# Module_CYW20737A1KML2G.net
KiCad netlist of a schematic drawn in Altium Designer
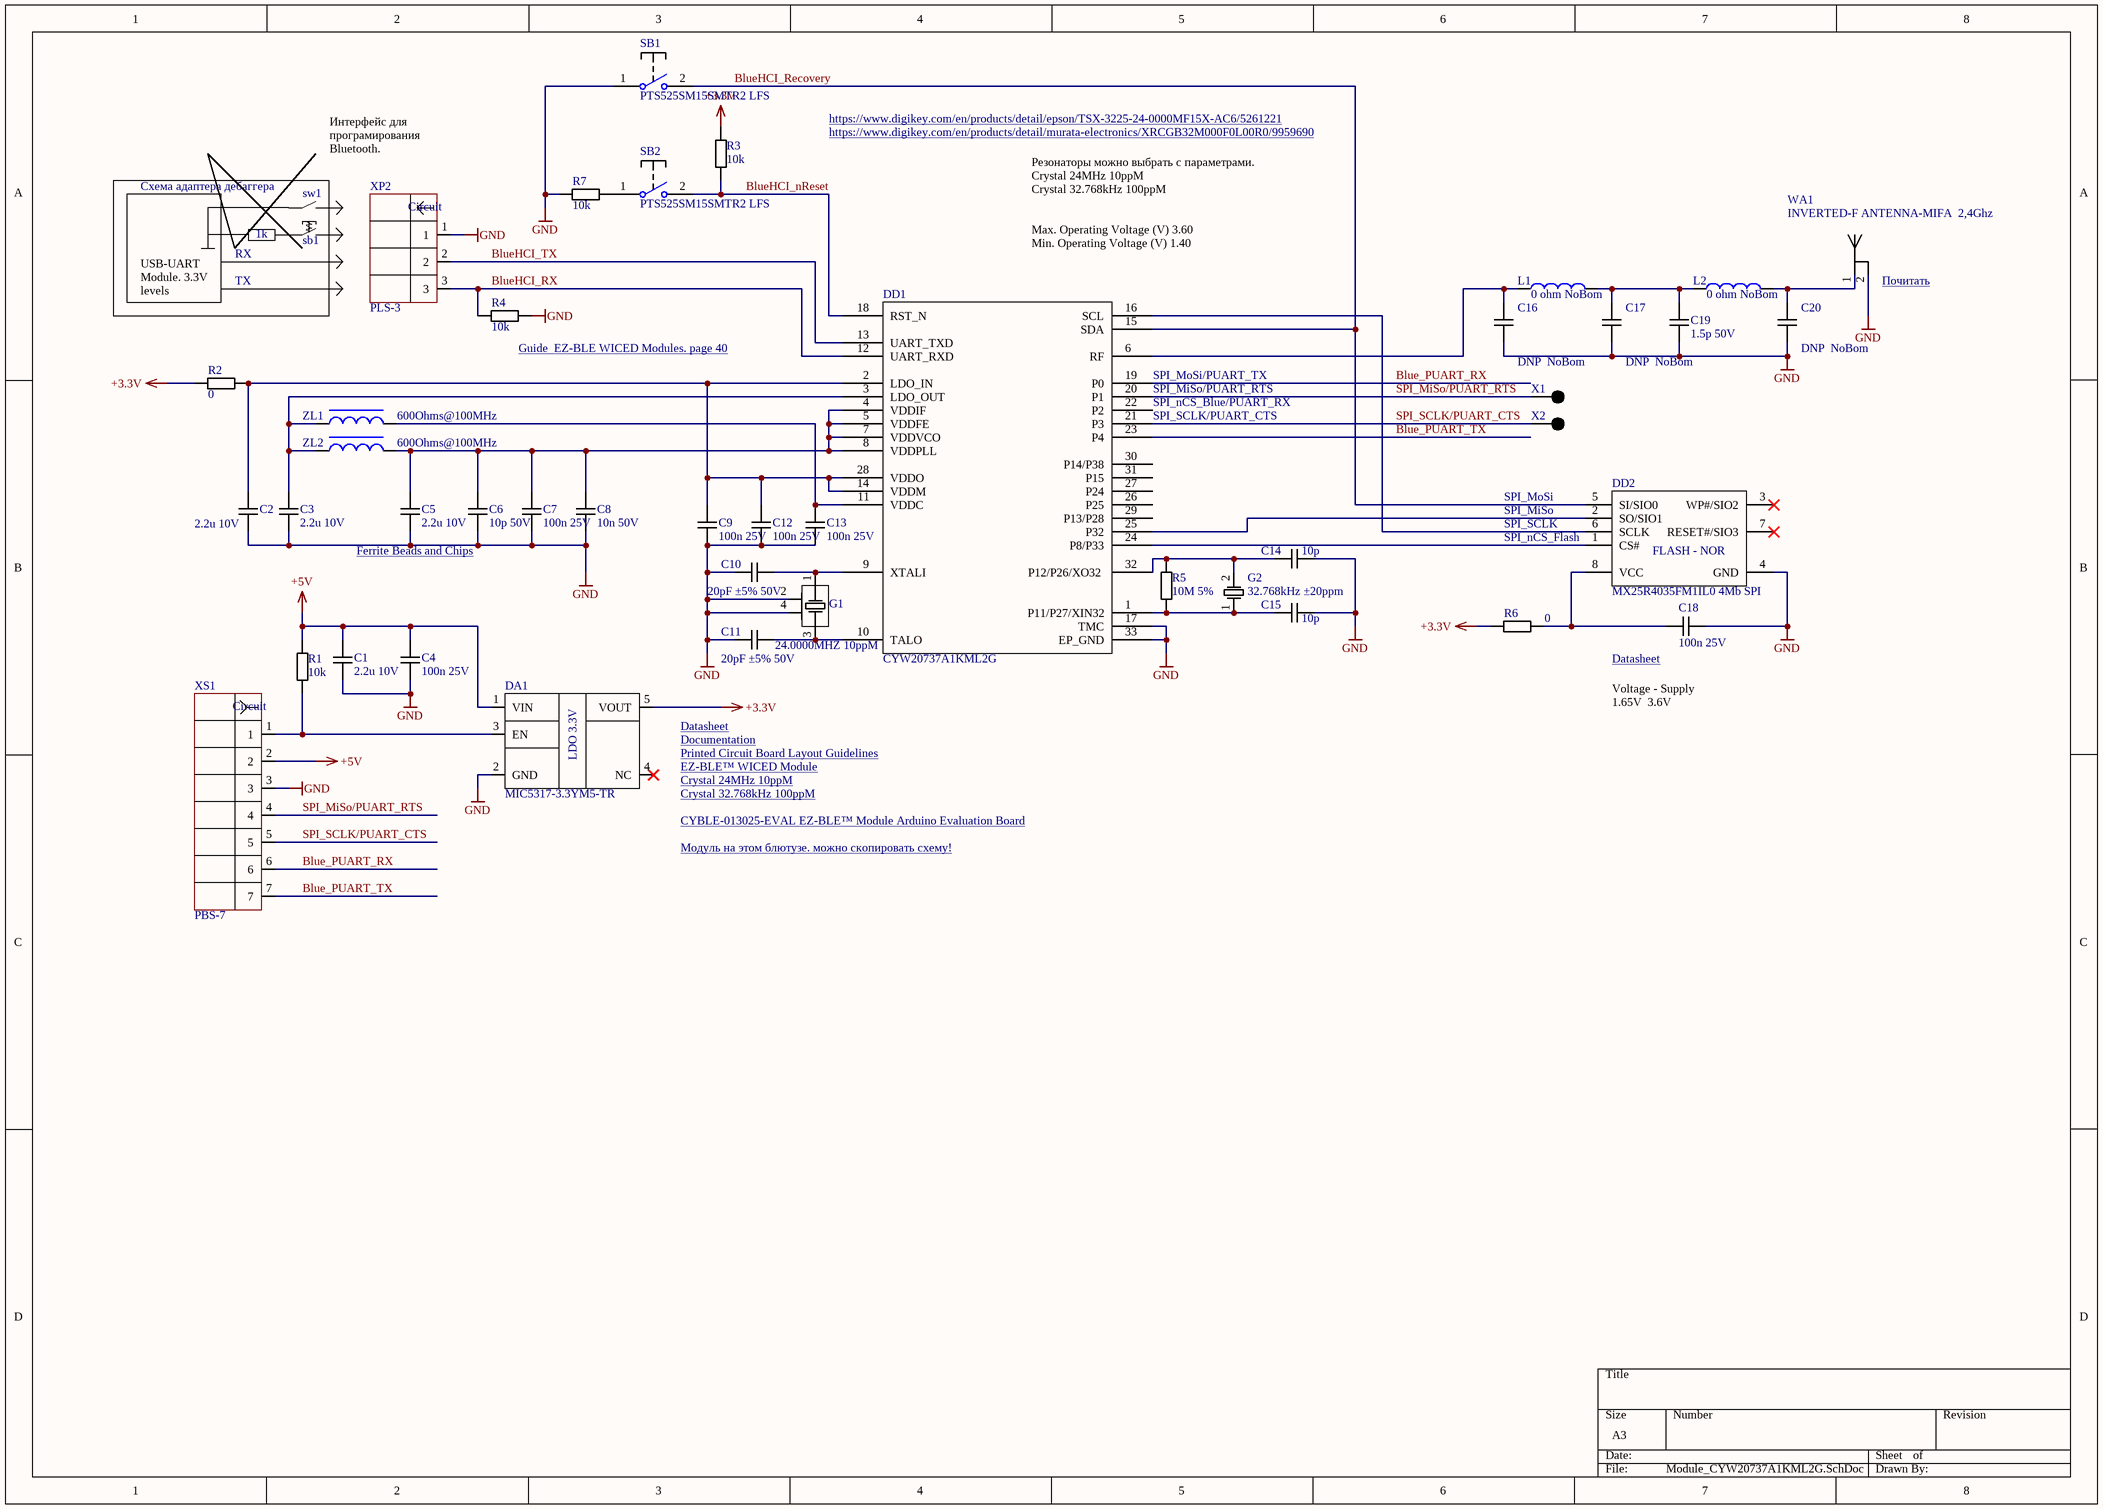
[diagram p0: Module_CYW20737A1KML2G.SchDoc]

(export (version "E")
  (design (tool "Eeschema 10.0.6"))
  (components
    (comp (ref "C1")
      (value "2.2u 10V")
      (footprint "CapKemet1005(0402)")
      (description "CAP CER 2.2uF 10V X5R 0402")
      (fields
        (field (name "PART NUMBER") "LMK105BJ225MV-F")
        (field (name "DIGI-KEY PART NUMBER") "587-3153-1-ND")
      )
      (libsource (lib "SssAccesDatbase") (part "Cap"))
    )
    (comp (ref "C2")
      (value "2.2u 10V")
      (footprint "CapKemet1005(0402)")
      (description "CAP CER 2.2uF 10V X5R 0402")
      (fields
        (field (name "PART NUMBER") "LMK105BJ225MV-F")
        (field (name "DIGI-KEY PART NUMBER") "587-3153-1-ND")
      )
      (libsource (lib "SssAccesDatbase") (part "Cap"))
    )
    (comp (ref "C3")
      (value "2.2u 10V")
      (footprint "CapKemet1005(0402)")
      (description "CAP CER 2.2uF 10V X5R 0402")
      (fields
        (field (name "PART NUMBER") "LMK105BJ225MV-F")
        (field (name "DIGI-KEY PART NUMBER") "587-3153-1-ND")
      )
      (libsource (lib "SssAccesDatbase") (part "Cap"))
    )
    (comp (ref "C4")
      (value "100n 25V")
      (footprint "CapKemet1005(0402)")
      (description "CAP CER 0.1UF 25V X7R 0402")
      (fields
        (field (name "PART NUMBER") "CL05B104KA5NNNC")
        (field (name "DIGI-KEY PART NUMBER") "1276-6720-1-ND")
      )
      (libsource (lib "SssAccesDatbase") (part "Cap"))
    )
    (comp (ref "C5")
      (value "2.2u 10V")
      (footprint "CapKemet1005(0402)")
      (description "CAP CER 2.2uF 10V X5R 0402")
      (fields
        (field (name "PART NUMBER") "LMK105BJ225MV-F")
        (field (name "DIGI-KEY PART NUMBER") "587-3153-1-ND")
      )
      (libsource (lib "SssAccesDatbase") (part "Cap"))
    )
    (comp (ref "C6")
      (value "10p 50V")
      (footprint "CapKemet1005(0402)")
      (description "CAP CER 10PF 50V C0G/NP0 0402")
      (fields
        (field (name "PART NUMBER") "CL05C100DB5NNNC")
        (field (name "DIGI-KEY PART NUMBER") "1276-1625-1-ND")
      )
      (libsource (lib "SssAccesDatbase") (part "Cap"))
    )
    (comp (ref "C7")
      (value "100n 25V")
      (footprint "CapKemet1005(0402)")
      (description "CAP CER 0.1UF 25V X7R 0402")
      (fields
        (field (name "PART NUMBER") "CL05B104KA5NNNC")
        (field (name "DIGI-KEY PART NUMBER") "1276-6720-1-ND")
      )
      (libsource (lib "SssAccesDatbase") (part "Cap"))
    )
    (comp (ref "C8")
      (value "10n 50V")
      (footprint "CapKemet1005(0402)")
      (description "CAP CER 10000PF 50V X7R 0402")
      (fields
        (field (name "PART NUMBER") "CL05B103KB5NNNC")
        (field (name "DIGI-KEY PART NUMBER") "1276-1028-1-ND")
      )
      (libsource (lib "SssAccesDatbase") (part "Cap"))
    )
    (comp (ref "C9")
      (value "100n 25V")
      (footprint "CapKemet1005(0402)")
      (description "CAP CER 0.1UF 25V X7R 0402")
      (fields
        (field (name "PART NUMBER") "CL05B104KA5NNNC")
        (field (name "DIGI-KEY PART NUMBER") "1276-6720-1-ND")
      )
      (libsource (lib "SssAccesDatbase") (part "Cap"))
    )
    (comp (ref "C10")
      (value "20pF ±5% 50V")
      (footprint "CapKemet1005(0402)")
      (description "20pF ±5% 50V Ceramic Capacitor C0G, NP0 0402 (1005 Metric)")
      (fields
        (field (name "PART NUMBER") "CC0402JRNPO9BN200")
        (field (name "DIGI-KEY PART NUMBER") "311-1417-1-ND")
      )
      (libsource (lib "SssAccesDatbase") (part "Cap"))
    )
    (comp (ref "C11")
      (value "20pF ±5% 50V")
      (footprint "CapKemet1005(0402)")
      (description "20pF ±5% 50V Ceramic Capacitor C0G, NP0 0402 (1005 Metric)")
      (fields
        (field (name "PART NUMBER") "CC0402JRNPO9BN200")
        (field (name "DIGI-KEY PART NUMBER") "311-1417-1-ND")
      )
      (libsource (lib "SssAccesDatbase") (part "Cap"))
    )
    (comp (ref "C12")
      (value "100n 25V")
      (footprint "CapKemet1005(0402)")
      (description "CAP CER 0.1UF 25V X7R 0402")
      (fields
        (field (name "PART NUMBER") "CL05B104KA5NNNC")
        (field (name "DIGI-KEY PART NUMBER") "1276-6720-1-ND")
      )
      (libsource (lib "SssAccesDatbase") (part "Cap"))
    )
    (comp (ref "C13")
      (value "100n 25V")
      (footprint "CapKemet1005(0402)")
      (description "CAP CER 0.1UF 25V X7R 0402")
      (fields
        (field (name "PART NUMBER") "CL05B104KA5NNNC")
        (field (name "DIGI-KEY PART NUMBER") "1276-6720-1-ND")
      )
      (libsource (lib "SssAccesDatbase") (part "Cap"))
    )
    (comp (ref "C14")
      (value "10p")
      (footprint "CapKemet1005(0402)")
      (description "10pF 0402 50V C0G  +/-0.5pF")
      (fields
        (field (name "PART NUMBER") "CC0402DRNPO9BN100")
        (field (name "MOUSER PART NUMBER") "603-CC402DRNPO9BN100")
      )
      (libsource (lib "SssAccesDatbase") (part "Cap"))
    )
    (comp (ref "C15")
      (value "10p")
      (footprint "CapKemet1005(0402)")
      (description "10pF 0402 50V C0G  +/-0.5pF")
      (fields
        (field (name "PART NUMBER") "CC0402DRNPO9BN100")
        (field (name "MOUSER PART NUMBER") "603-CC402DRNPO9BN100")
      )
      (libsource (lib "SssAccesDatbase") (part "Cap"))
    )
    (comp (ref "C16")
      (value "DNP  NoBom")
      (footprint "CapKemet1005(0402)")
      (description "150pF 0402 50V NP0  +/-5%")
      (fields
        (field (name "PART NUMBER") "GCM1555C1H151JA16D")
        (field (name "MOUSER PART NUMBER") "81-GCM1555C1H151J16D")
      )
      (libsource (lib "SssAccesDatbase") (part "Cap"))
    )
    (comp (ref "C17")
      (value "DNP  NoBom")
      (footprint "CapKemet1005(0402)")
      (description "150pF 0402 50V NP0  +/-5%")
      (fields
        (field (name "PART NUMBER") "GCM1555C1H151JA16D")
        (field (name "MOUSER PART NUMBER") "81-GCM1555C1H151J16D")
      )
      (libsource (lib "SssAccesDatbase") (part "Cap"))
    )
    (comp (ref "C18")
      (value "100n 25V")
      (footprint "CapKemet1005(0402)")
      (description "CAP CER 0.1UF 25V X7R 0402")
      (fields
        (field (name "PART NUMBER") "CL05B104KA5NNNC")
        (field (name "DIGI-KEY PART NUMBER") "1276-6720-1-ND")
      )
      (libsource (lib "SssAccesDatbase") (part "Cap"))
    )
    (comp (ref "C19")
      (value "1.5p 50V")
      (footprint "CapKemet1005(0402)")
      (description "CAP CER 1.5pF 50V COG 0402 ±0.1pF")
      (fields
        (field (name "PART NUMBER") "CL05C1R5BB5NNNC")
        (field (name "DIGI-KEY PART NUMBER") "1276-1656-1-ND")
      )
      (libsource (lib "SssAccesDatbase") (part "Cap"))
    )
    (comp (ref "C20")
      (value "DNP  NoBom")
      (footprint "CapKemet1005(0402)")
      (description "150pF 0402 50V NP0  +/-5%")
      (fields
        (field (name "PART NUMBER") "GCM1555C1H151JA16D")
        (field (name "MOUSER PART NUMBER") "81-GCM1555C1H151J16D")
      )
      (libsource (lib "SssAccesDatbase") (part "Cap"))
    )
    (comp (ref "DA1")
      (value "MIC5317-3.3YM5-TR")
      (footprint "SOT-23-OT5_N")
      (description "Linear Voltage Regulator IC 1 Output 150mA SOT-23-5")
      (fields (field (name "DIGI-KEY PART NUMBER") "MIC5317-3.3YM5-CT-ND"))
      (libsource (lib "SssAccesDatbase") (part "MIC5317-3.3YM5-TR"))
    )
    (comp (ref "DD1")
      (value "CYW20737A1KML2G")
      (footprint "QFN5X5-32_N")
      (description "IC RF TXRX+MCU BLUETOOTH 32VFQFN")
      (fields (field (name "DIGI-KEY PART NUMBER") "2015-CYW20737A1KML2G-ND"))
      (libsource (lib "SssAccesDatbase") (part "CYW20737A1KML2G"))
    )
    (comp (ref "DD2")
      (value "MX25R4035FM1IL0 4Mb SPI")
      (footprint "MCHP-SOIC-SN8_M")
      (description "IC FLASH 4M SPI 33MHZ 8SOP")
      (fields (field (name "PART NUMBER") "MX25R4035FM1IL0"))
      (libsource (lib "SssAccesDatbase") (part "MX25R4035FM1IL0"))
    )
    (comp (ref "G1")
      (value "24.0000MHZ 10ppM")
      (footprint "TSX-3225")
      (description "24MHz ±10ppm Crystal 9pF 40 Ohms 4-SMD, No Lead")
      (fields
        (field (name "PART NUMBER") "TSX-3225 24.0000MF15X-AC6")
        (field (name "DIGI-KEY PART NUMBER") "SER4180CT-ND")
      )
      (libsource (lib "SssAccesDatbase") (part "CTX957CT"))
    )
    (comp (ref "G2")
      (value "32.768kHz ±20ppm")
      (footprint "VMK3-9005")
      (description "32.768kHz ±20ppm Crystal   2-SMD, No Lead")
      (fields
        (field (name "PART NUMBER") "VMK3-9005-32K7680000")
        (field (name "DIGI-KEY PART NUMBER") "150-VMK3-9005-32K7680000CT-ND")
      )
      (libsource (lib "SssAccesDatbase") (part "Crystal"))
    )
    (comp (ref "L1")
      (value "0 ohm NoBom")
      (footprint "INDC1608(0603)N")
      (description "Fixed Inductors 270nH 2% -40C +125C")
      (fields
        (field (name "PART NUMBER") "AISC-0603-R27G-T")
        (field (name "MOUSER PART NUMBER") "815-AISC0603R27GT")
      )
      (libsource (lib "SssAccesDatbase") (part "L"))
    )
    (comp (ref "L2")
      (value "0 ohm NoBom")
      (footprint "INDC1608(0603)N")
      (description "Fixed Inductors 270nH 2% -40C +125C")
      (fields
        (field (name "PART NUMBER") "AISC-0603-R27G-T")
        (field (name "MOUSER PART NUMBER") "815-AISC0603R27GT")
      )
      (libsource (lib "SssAccesDatbase") (part "L"))
    )
    (comp (ref "R1")
      (value "10k")
      (footprint "REZKemet 0402")
      (description "RES SMD 5.1K OHM 1% 1/10W 0402")
      (fields
        (field (name "PART NUMBER") "RESC1005(0402)")
        (field (name "MANUFACTURER PART NUMBER") "ERJ-2RKF5101X")
      )
      (libsource (lib "SssAccesDatbase") (part "Resistor general"))
    )
    (comp (ref "R2")
      (value "0")
      (footprint "REZKemet 0402")
      (description "RES SMD 0402 0 Ohm")
      (fields
        (field (name "PART NUMBER") "RMCF0402ZT0R00")
        (field (name "MOUSER PART NUMBER") "RMCF0402ZT0R00CT-ND")
      )
      (libsource (lib "") (part "Resistor general_4"))
    )
    (comp (ref "R3")
      (value "10k")
      (footprint "REZKemet 0402")
      (description "RES SMD 5.1K OHM 1% 1/10W 0402")
      (fields
        (field (name "PART NUMBER") "RESC1005(0402)")
        (field (name "MANUFACTURER PART NUMBER") "ERJ-2RKF5101X")
      )
      (libsource (lib "SssAccesDatbase") (part "Resistor general"))
    )
    (comp (ref "R4")
      (value "10k")
      (footprint "REZKemet 0402")
      (description "RES SMD 5.1K OHM 1% 1/10W 0402")
      (fields
        (field (name "PART NUMBER") "RESC1005(0402)")
        (field (name "MANUFACTURER PART NUMBER") "ERJ-2RKF5101X")
      )
      (libsource (lib "") (part "Resistor general_1"))
    )
    (comp (ref "R5")
      (value "10M 5%")
      (footprint "REZKemet 0402")
      (description "RES SMD 0402 10 MOhm 5% 200ppm")
      (fields
        (field (name "PART NUMBER") "RMCF0402JT10M0")
        (field (name "DIGI-KEY PART NUMBER") "RMCF0402JT10M0CT-ND")
      )
      (libsource (lib "") (part "Resistor general_2"))
    )
    (comp (ref "R6")
      (value "0")
      (footprint "REZKemet 0402")
      (description "RES SMD 0402 0 Ohm")
      (fields
        (field (name "PART NUMBER") "RMCF0402ZT0R00")
        (field (name "MOUSER PART NUMBER") "RMCF0402ZT0R00CT-ND")
      )
      (libsource (lib "") (part "Resistor general_3"))
    )
    (comp (ref "R7")
      (value "10k")
      (footprint "REZKemet 0402")
      (description "RES SMD 5.1K OHM 1% 1/10W 0402")
      (fields
        (field (name "PART NUMBER") "RESC1005(0402)")
        (field (name "MANUFACTURER PART NUMBER") "ERJ-2RKF5101X")
      )
      (libsource (lib "") (part "Resistor general_1"))
    )
    (comp (ref "SB1")
      (value "PTS525SM15SMTR2 LFS")
      (footprint "TACT_SWITCH KPT1187B")
      (description "SWITCH TACTILE SPST-NO 0.02A 15V")
      (fields (field (name "DIGI-KEY PART NUMBER") "CKN9104CT-ND"))
      (libsource (lib "SssAccesDatbase") (part "TACT_SWITCH KPT1187B"))
    )
    (comp (ref "SB2")
      (value "PTS525SM15SMTR2 LFS")
      (footprint "TACT_SWITCH KPT1187B")
      (description "SWITCH TACTILE SPST-NO 0.02A 15V")
      (fields (field (name "DIGI-KEY PART NUMBER") "CKN9104CT-ND"))
      (libsource (lib "SssAccesDatbase") (part "TACT_SWITCH KPT1187B"))
    )
    (comp (ref "WA1")
      (value "INVERTED-F ANTENNA-MIFA  2,4Ghz")
      (footprint "INVERTED-F ANTENNA-MIFA")
      (libsource (lib "SssAccesDatbase") (part "WA_2pin_tie"))
    )
    (comp (ref "X1")
      (value "PLLS1.27-1-TOP-R")
      (footprint "PLLS1.27-1-TOP-R")
      (libsource (lib "SssAccesDatbase") (part "X1_1"))
    )
    (comp (ref "X2")
      (value "PLLS1.27-1-TOP-R")
      (footprint "PLLS1.27-1-TOP-R")
      (libsource (lib "SssAccesDatbase") (part "X1_1"))
    )
    (comp (ref "XP2")
      (value "PLS-3")
      (footprint "PLS-3-3D")
      (description "CONN HEADER VERT 3POS 2.54MM")
      (fields
        (field (name "DIGI-KEY PART NUMBER") "1849-1003-ND")
        (field (name "MANUFACTURER PART NUMBER") "PR20203VBNN")
      )
      (libsource (lib "SssAccesDatbase") (part "XP-3"))
    )
    (comp (ref "XS1")
      (value "PBS-7")
      (footprint "PBS-7-3D")
      (libsource (lib "SssAccesDatbase") (part "XS-7"))
    )
    (comp (ref "ZL1")
      (value "600Ohms@100MHz")
      (footprint "Ferrite1005(0402)")
      (description "FERRITE BEAD 600 OHM 0402 1LN")
      (fields
        (field (name "PART NUMBER") "MMZ1005S601CT000")
        (field (name "DIGI-KEY PART NUMBER") "445-2162-1-ND")
      )
      (libsource (lib "SssAccesDatbase") (part "ZL"))
    )
    (comp (ref "ZL2")
      (value "600Ohms@100MHz")
      (footprint "Ferrite1005(0402)")
      (description "FERRITE BEAD 600 OHM 0402 1LN")
      (fields
        (field (name "PART NUMBER") "MMZ1005S601CT000")
        (field (name "DIGI-KEY PART NUMBER") "445-2162-1-ND")
      )
      (libsource (lib "SssAccesDatbase") (part "ZL"))
    )
  )
  (nets
    (net (code "1") (name "+3.3V") (class "Default")
      (node (ref "DA1") (pin "5") (pinfunction "VOUT_5") (pintype "passive"))
      (node (ref "R2") (pin "2") (pinfunction "2_2") (pintype "passive"))
      (node (ref "R3") (pin "2") (pinfunction "2_2") (pintype "passive"))
      (node (ref "R6") (pin "1") (pinfunction "1_1") (pintype "passive"))
    )
    (net (code "2") (name "+5V") (class "Default")
      (node (ref "C1") (pin "2") (pinfunction "2_2") (pintype "passive"))
      (node (ref "C4") (pin "2") (pinfunction "2_2") (pintype "passive"))
      (node (ref "DA1") (pin "1") (pinfunction "VIN_1") (pintype "passive"))
      (node (ref "R1") (pin "2") (pinfunction "2_2") (pintype "passive"))
      (node (ref "XS1") (pin "2") (pinfunction "2_2") (pintype "passive"))
    )
    (net (code "3") (name "/BlueHCI_RX") (class "Default")
      (node (ref "DD1") (pin "12") (pinfunction "UART_RXD_12") (pintype "passive"))
      (node (ref "R4") (pin "2") (pinfunction "2_2") (pintype "passive"))
      (node (ref "XP2") (pin "3") (pinfunction "3_3") (pintype "passive"))
    )
    (net (code "4") (name "/BlueHCI_Recovery") (class "Default")
      (node (ref "DD1") (pin "15") (pinfunction "SDA_15") (pintype "passive"))
      (node (ref "DD2") (pin "5") (pinfunction "SI/SIO0_5") (pintype "passive"))
      (node (ref "SB1") (pin "2") (pinfunction "NO_2") (pintype "passive"))
    )
    (net (code "5") (name "/BlueHCI_TX") (class "Default")
      (node (ref "DD1") (pin "13") (pinfunction "UART_TXD_13") (pintype "passive"))
      (node (ref "XP2") (pin "2") (pinfunction "2_2") (pintype "passive"))
    )
    (net (code "6") (name "/BlueHCI_nReset") (class "Default")
      (node (ref "DD1") (pin "18") (pinfunction "RST_N_18") (pintype "passive"))
      (node (ref "R3") (pin "1") (pinfunction "1_1") (pintype "passive"))
      (node (ref "SB2") (pin "2") (pinfunction "NO_2") (pintype "passive"))
    )
    (net (code "7") (name "/Blue_PUART_RX") (class "Default")
      (node (ref "DD1") (pin "19") (pinfunction "P0_19") (pintype "passive"))
      (node (ref "XS1") (pin "6") (pinfunction "6_6") (pintype "passive"))
    )
    (net (code "8") (name "/Blue_PUART_TX") (class "Default")
      (node (ref "DD1") (pin "23") (pinfunction "P4_23") (pintype "passive"))
      (node (ref "XS1") (pin "7") (pinfunction "7_7") (pintype "passive"))
    )
    (net (code "9") (name "/SPI_MiSo{slash}PUART_RTS") (class "Default")
      (node (ref "DD1") (pin "20") (pinfunction "P1_20") (pintype "passive"))
      (node (ref "X1") (pin "1") (pinfunction "1_1") (pintype "passive"))
      (node (ref "XS1") (pin "4") (pinfunction "4_4") (pintype "passive"))
    )
    (net (code "10") (name "/SPI_SCLK{slash}PUART_CTS") (class "Default")
      (node (ref "DD1") (pin "21") (pinfunction "P3_21") (pintype "passive"))
      (node (ref "X2") (pin "1") (pinfunction "1_1") (pintype "passive"))
      (node (ref "XS1") (pin "5") (pinfunction "5_5") (pintype "passive"))
    )
    (net (code "11") (name "GND") (class "Default")
      (node (ref "C1") (pin "1") (pinfunction "1_1") (pintype "passive"))
      (node (ref "C10") (pin "1") (pinfunction "1_1") (pintype "passive"))
      (node (ref "C11") (pin "1") (pinfunction "1_1") (pintype "passive"))
      (node (ref "C12") (pin "1") (pinfunction "1_1") (pintype "passive"))
      (node (ref "C13") (pin "1") (pinfunction "1_1") (pintype "passive"))
      (node (ref "C14") (pin "1") (pinfunction "1_1") (pintype "passive"))
      (node (ref "C15") (pin "1") (pinfunction "1_1") (pintype "passive"))
      (node (ref "C16") (pin "1") (pinfunction "1_1") (pintype "passive"))
      (node (ref "C17") (pin "1") (pinfunction "1_1") (pintype "passive"))
      (node (ref "C18") (pin "1") (pinfunction "1_1") (pintype "passive"))
      (node (ref "C19") (pin "1") (pinfunction "1_1") (pintype "passive"))
      (node (ref "C2") (pin "1") (pinfunction "1_1") (pintype "passive"))
      (node (ref "C20") (pin "1") (pinfunction "1_1") (pintype "passive"))
      (node (ref "C3") (pin "1") (pinfunction "1_1") (pintype "passive"))
      (node (ref "C4") (pin "1") (pinfunction "1_1") (pintype "passive"))
      (node (ref "C5") (pin "1") (pinfunction "1_1") (pintype "passive"))
      (node (ref "C6") (pin "1") (pinfunction "1_1") (pintype "passive"))
      (node (ref "C7") (pin "1") (pinfunction "1_1") (pintype "passive"))
      (node (ref "C8") (pin "1") (pinfunction "1_1") (pintype "passive"))
      (node (ref "C9") (pin "1") (pinfunction "1_1") (pintype "passive"))
      (node (ref "DA1") (pin "2") (pinfunction "GND_2") (pintype "passive"))
      (node (ref "DD1") (pin "17") (pinfunction "TMC_17") (pintype "passive"))
      (node (ref "DD1") (pin "33") (pinfunction "EP_GND_33") (pintype "passive"))
      (node (ref "DD2") (pin "4") (pinfunction "GND_4") (pintype "passive"))
      (node (ref "G1") (pin "2") (pinfunction "2_2") (pintype "passive"))
      (node (ref "G1") (pin "4") (pinfunction "4_4") (pintype "passive"))
      (node (ref "R4") (pin "1") (pinfunction "1_1") (pintype "passive"))
      (node (ref "R7") (pin "2") (pinfunction "2_2") (pintype "passive"))
      (node (ref "SB1") (pin "1") (pinfunction "COMMON_1") (pintype "passive"))
      (node (ref "WA1") (pin "2") (pinfunction "2_2") (pintype "passive"))
      (node (ref "XP2") (pin "1") (pinfunction "1_1") (pintype "passive"))
      (node (ref "XS1") (pin "3") (pinfunction "3_3") (pintype "passive"))
    )
    (net (code "12") (name "Net-(C17-Pad2)") (class "Default")
      (node (ref "C17") (pin "2") (pinfunction "2_2") (pintype "passive"))
      (node (ref "C19") (pin "2") (pinfunction "2_2") (pintype "passive"))
      (node (ref "L1") (pin "2") (pinfunction "2_2") (pintype "passive"))
      (node (ref "L2") (pin "1") (pinfunction "1_1") (pintype "passive"))
    )
    (net (code "13") (name "Net-(C20-Pad2)") (class "Default")
      (node (ref "C20") (pin "2") (pinfunction "2_2") (pintype "passive"))
      (node (ref "L2") (pin "2") (pinfunction "2_2") (pintype "passive"))
      (node (ref "WA1") (pin "1") (pinfunction "1_1") (pintype "passive"))
    )
    (net (code "14") (name "Net-(DA1-EN)") (class "Default")
      (node (ref "DA1") (pin "3") (pinfunction "EN_3") (pintype "passive"))
      (node (ref "R1") (pin "1") (pinfunction "1_1") (pintype "passive"))
      (node (ref "XS1") (pin "1") (pinfunction "1_1") (pintype "passive"))
    )
    (net (code "15") (name "Net-(DD1-LDO_IN)") (class "Default")
      (node (ref "C12") (pin "2") (pinfunction "2_2") (pintype "passive"))
      (node (ref "C2") (pin "2") (pinfunction "2_2") (pintype "passive"))
      (node (ref "C9") (pin "2") (pinfunction "2_2") (pintype "passive"))
      (node (ref "DD1") (pin "14") (pinfunction "VDDM_14") (pintype "passive"))
      (node (ref "DD1") (pin "2") (pinfunction "LDO_IN_2") (pintype "passive"))
      (node (ref "DD1") (pin "28") (pinfunction "VDDO_28") (pintype "passive"))
      (node (ref "R2") (pin "1") (pinfunction "1_1") (pintype "passive"))
    )
    (net (code "16") (name "Net-(DD1-LDO_OUT)") (class "Default")
      (node (ref "C3") (pin "2") (pinfunction "2_2") (pintype "passive"))
      (node (ref "DD1") (pin "3") (pinfunction "LDO_OUT_3") (pintype "passive"))
      (node (ref "ZL1") (pin "1") (pinfunction "1_1") (pintype "passive"))
      (node (ref "ZL2") (pin "1") (pinfunction "1_1") (pintype "passive"))
    )
    (net (code "17") (name "Net-(DD1-P8{slash}P33)") (class "Default")
      (node (ref "DD1") (pin "24") (pinfunction "P8/P33_24") (pintype "passive"))
      (node (ref "DD2") (pin "1") (pinfunction "CS#_1") (pintype "passive"))
    )
    (net (code "18") (name "Net-(DD1-P11{slash}P27{slash}XIN32)") (class "Default")
      (node (ref "C15") (pin "2") (pinfunction "2_2") (pintype "passive"))
      (node (ref "DD1") (pin "1") (pinfunction "P11/P27/XIN32_1") (pintype "passive"))
      (node (ref "G2") (pin "1") (pinfunction "1_1") (pintype "passive"))
      (node (ref "R5") (pin "1") (pinfunction "1_1") (pintype "passive"))
    )
    (net (code "19") (name "Net-(DD1-P12{slash}P26{slash}XO32)") (class "Default")
      (node (ref "C14") (pin "2") (pinfunction "2_2") (pintype "passive"))
      (node (ref "DD1") (pin "32") (pinfunction "P12/P26/XO32_32") (pintype "passive"))
      (node (ref "G2") (pin "2") (pinfunction "2_2") (pintype "passive"))
      (node (ref "R5") (pin "2") (pinfunction "2_2") (pintype "passive"))
    )
    (net (code "20") (name "Net-(DD1-P32)") (class "Default")
      (node (ref "DD1") (pin "25") (pinfunction "P32_25") (pintype "passive"))
      (node (ref "DD2") (pin "2") (pinfunction "SO/SIO1_2") (pintype "passive"))
    )
    (net (code "21") (name "Net-(DD1-RF)") (class "Default")
      (node (ref "C16") (pin "2") (pinfunction "2_2") (pintype "passive"))
      (node (ref "DD1") (pin "6") (pinfunction "RF_6") (pintype "passive"))
      (node (ref "L1") (pin "1") (pinfunction "1_1") (pintype "passive"))
    )
    (net (code "22") (name "Net-(DD1-SCL)") (class "Default")
      (node (ref "DD1") (pin "16") (pinfunction "SCL_16") (pintype "passive"))
      (node (ref "DD2") (pin "6") (pinfunction "SCLK_6") (pintype "passive"))
    )
    (net (code "23") (name "Net-(DD1-TALO)") (class "Default")
      (node (ref "C11") (pin "2") (pinfunction "2_2") (pintype "passive"))
      (node (ref "DD1") (pin "10") (pinfunction "TALO_10") (pintype "passive"))
      (node (ref "G1") (pin "3") (pinfunction "3_3") (pintype "passive"))
    )
    (net (code "24") (name "Net-(DD1-VDDC)") (class "Default")
      (node (ref "C13") (pin "2") (pinfunction "2_2") (pintype "passive"))
      (node (ref "DD1") (pin "11") (pinfunction "VDDC_11") (pintype "passive"))
      (node (ref "ZL1") (pin "2") (pinfunction "2_2") (pintype "passive"))
    )
    (net (code "25") (name "Net-(DD1-VDDFE)") (class "Default")
      (node (ref "C5") (pin "2") (pinfunction "2_2") (pintype "passive"))
      (node (ref "C6") (pin "2") (pinfunction "2_2") (pintype "passive"))
      (node (ref "C7") (pin "2") (pinfunction "2_2") (pintype "passive"))
      (node (ref "C8") (pin "2") (pinfunction "2_2") (pintype "passive"))
      (node (ref "DD1") (pin "4") (pinfunction "VDDIF_4") (pintype "passive"))
      (node (ref "DD1") (pin "5") (pinfunction "VDDFE_5") (pintype "passive"))
      (node (ref "DD1") (pin "7") (pinfunction "VDDVCO_7") (pintype "passive"))
      (node (ref "DD1") (pin "8") (pinfunction "VDDPLL_8") (pintype "passive"))
      (node (ref "ZL2") (pin "2") (pinfunction "2_2") (pintype "passive"))
    )
    (net (code "26") (name "Net-(DD1-XTALI)") (class "Default")
      (node (ref "C10") (pin "2") (pinfunction "2_2") (pintype "passive"))
      (node (ref "DD1") (pin "9") (pinfunction "XTALI_9") (pintype "passive"))
      (node (ref "G1") (pin "1") (pinfunction "1_1") (pintype "passive"))
    )
    (net (code "27") (name "Net-(DD2-VCC)") (class "Default")
      (node (ref "C18") (pin "2") (pinfunction "2_2") (pintype "passive"))
      (node (ref "DD2") (pin "8") (pinfunction "VCC_8") (pintype "passive"))
      (node (ref "R6") (pin "2") (pinfunction "2_2") (pintype "passive"))
    )
    (net (code "28") (name "Net-(SB2-COMMON)") (class "Default")
      (node (ref "R7") (pin "1") (pinfunction "1_1") (pintype "passive"))
      (node (ref "SB2") (pin "1") (pinfunction "COMMON_1") (pintype "passive"))
    )
    (net (code "29") (name "unconnected-(DA1-NC-Pad4)") (class "Default")
      (node (ref "DA1") (pin "4") (pinfunction "NC_4") (pintype "passive+no_connect"))
    )
    (net (code "30") (name "unconnected-(DD1-P2-Pad22)") (class "Default")
      (node (ref "DD1") (pin "22") (pinfunction "P2_22") (pintype "passive"))
    )
    (net (code "31") (name "unconnected-(DD1-P13{slash}P28-Pad29)") (class "Default")
      (node (ref "DD1") (pin "29") (pinfunction "P13/P28_29") (pintype "passive"))
    )
    (net (code "32") (name "unconnected-(DD1-P14{slash}P38-Pad30)") (class "Default")
      (node (ref "DD1") (pin "30") (pinfunction "P14/P38_30") (pintype "passive"))
    )
    (net (code "33") (name "unconnected-(DD1-P15-Pad31)") (class "Default")
      (node (ref "DD1") (pin "31") (pinfunction "P15_31") (pintype "passive"))
    )
    (net (code "34") (name "unconnected-(DD1-P24-Pad27)") (class "Default")
      (node (ref "DD1") (pin "27") (pinfunction "P24_27") (pintype "passive"))
    )
    (net (code "35") (name "unconnected-(DD1-P25-Pad26)") (class "Default")
      (node (ref "DD1") (pin "26") (pinfunction "P25_26") (pintype "passive"))
    )
    (net (code "36") (name "unconnected-(DD2-RESET#{slash}SIO3-Pad7)") (class "Default")
      (node (ref "DD2") (pin "7") (pinfunction "RESET#/SIO3_7") (pintype "passive+no_connect"))
    )
    (net (code "37") (name "unconnected-(DD2-WP#{slash}SIO2-Pad3)") (class "Default")
      (node (ref "DD2") (pin "3") (pinfunction "WP#/SIO2_3") (pintype "passive+no_connect"))
    )
  )
)
